# Condicionamento.net
KiCad netlist of a schematic drawn in Altium Designer
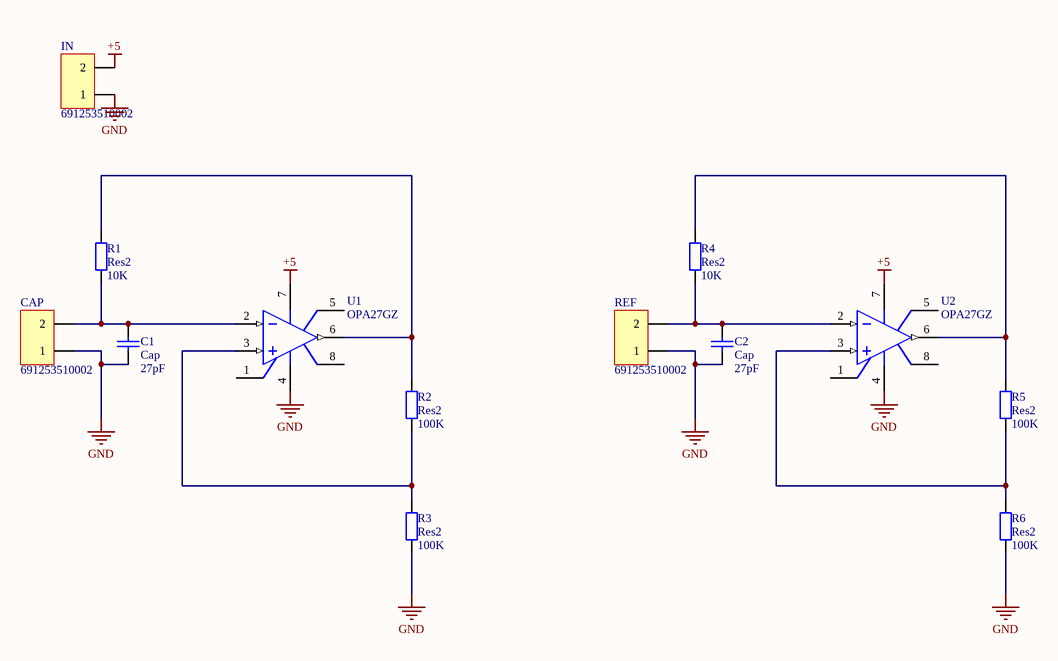
[diagram p0: Condicionamento.SchDoc]

(export (version "E")
  (design (tool "Eeschema 10.0.6"))
  (components
    (comp (ref "C1")
      (value "Cap")
      (footprint "RAD-0.3")
      (description "Capacitor")
      (fields (field (name "ALTIUM_VALUE") "27pF") (field (name "PUBLISHER") "Altium Limited"))
      (libsource (lib "Miscellaneous Devices") (part "Cap"))
    )
    (comp (ref "C2")
      (value "Cap")
      (footprint "RAD-0.3")
      (description "Capacitor")
      (fields (field (name "ALTIUM_VALUE") "27pF") (field (name "PUBLISHER") "Altium Limited"))
      (libsource (lib "Miscellaneous Devices") (part "Cap"))
    )
    (comp (ref "CAP")
      (value "691253510002")
      (footprint "691253510002")
      (description "Horizontal Cable Entry with Rising Cage Clamp, Serie 2535 - 5.08mm")
      (fields (field (name "MANUFACTURER") "Wurth Elektronik") (field (name "CREATED BY") "Baojun Chen"))
      (libsource (lib "WE_WR-TBL_Rising Cage System_5.08 mm_rev15b") (part "691253510002"))
    )
    (comp (ref "IN")
      (value "691253510002")
      (footprint "691253510002")
      (description "Horizontal Cable Entry with Rising Cage Clamp, Serie 2535 - 5.08mm")
      (fields (field (name "MANUFACTURER") "Wurth Elektronik") (field (name "CREATED BY") "Baojun Chen"))
      (libsource (lib "WE_WR-TBL_Rising Cage System_5.08 mm_rev15b") (part "691253510002"))
    )
    (comp (ref "R1")
      (value "Res2")
      (footprint "AXIAL-0.4")
      (description "Resistor")
      (fields (field (name "ALTIUM_VALUE") "10K") (field (name "PUBLISHER") "Altium Limited"))
      (libsource (lib "Miscellaneous Devices") (part "Res2"))
    )
    (comp (ref "R2")
      (value "Res2")
      (footprint "AXIAL-0.4")
      (description "Resistor")
      (fields (field (name "ALTIUM_VALUE") "100K") (field (name "PUBLISHER") "Altium Limited"))
      (libsource (lib "Miscellaneous Devices") (part "Res2"))
    )
    (comp (ref "R3")
      (value "Res2")
      (footprint "AXIAL-0.4")
      (description "Resistor")
      (fields (field (name "ALTIUM_VALUE") "100K") (field (name "PUBLISHER") "Altium Limited"))
      (libsource (lib "Miscellaneous Devices") (part "Res2"))
    )
    (comp (ref "R4")
      (value "Res2")
      (footprint "AXIAL-0.4")
      (description "Resistor")
      (fields (field (name "ALTIUM_VALUE") "10K") (field (name "PUBLISHER") "Altium Limited"))
      (libsource (lib "Miscellaneous Devices") (part "Res2"))
    )
    (comp (ref "R5")
      (value "Res2")
      (footprint "AXIAL-0.4")
      (description "Resistor")
      (fields (field (name "ALTIUM_VALUE") "100K") (field (name "PUBLISHER") "Altium Limited"))
      (libsource (lib "Miscellaneous Devices") (part "Res2"))
    )
    (comp (ref "R6")
      (value "Res2")
      (footprint "AXIAL-0.4")
      (description "Resistor")
      (fields (field (name "ALTIUM_VALUE") "100K") (field (name "PUBLISHER") "Altium Limited"))
      (libsource (lib "Miscellaneous Devices") (part "Res2"))
    )
    (comp (ref "REF")
      (value "691253510002")
      (footprint "691253510002")
      (description "Horizontal Cable Entry with Rising Cage Clamp, Serie 2535 - 5.08mm")
      (fields (field (name "MANUFACTURER") "Wurth Elektronik") (field (name "CREATED BY") "Baojun Chen"))
      (libsource (lib "WE_WR-TBL_Rising Cage System_5.08 mm_rev15b") (part "691253510002"))
    )
    (comp (ref "U1")
      (value "OPA27GZ")
      (footprint "ZZ161")
      (description "Ultra-Low-Noise Precision Operational Amplifiers")
      (fields (field (name "PUBLISHER") "Altium Limited"))
      (libsource (lib "BB Operational Amplifier") (part "OPA27GZ"))
    )
    (comp (ref "U2")
      (value "OPA27GZ")
      (footprint "ZZ161")
      (description "Ultra-Low-Noise Precision Operational Amplifiers")
      (fields (field (name "PUBLISHER") "Altium Limited"))
      (libsource (lib "BB Operational Amplifier") (part "OPA27GZ"))
    )
  )
  (nets
    (net (code "1") (name "+5") (class "Default")
      (node (ref "IN") (pin "2") (pinfunction "2_2") (pintype "passive"))
      (node (ref "U1") (pin "7") (pinfunction "V+_7") (pintype "power_in"))
      (node (ref "U2") (pin "7") (pinfunction "V+_7") (pintype "power_in"))
    )
    (net (code "2") (name "GND") (class "Default")
      (node (ref "C1") (pin "1") (pinfunction "1_1") (pintype "passive"))
      (node (ref "C2") (pin "1") (pinfunction "1_1") (pintype "passive"))
      (node (ref "CAP") (pin "1") (pinfunction "1_1") (pintype "passive"))
      (node (ref "IN") (pin "1") (pinfunction "1_1") (pintype "passive"))
      (node (ref "R3") (pin "1") (pinfunction "1_1") (pintype "passive"))
      (node (ref "R6") (pin "1") (pinfunction "1_1") (pintype "passive"))
      (node (ref "REF") (pin "1") (pinfunction "1_1") (pintype "passive"))
      (node (ref "U1") (pin "4") (pinfunction "V-_4") (pintype "power_in"))
      (node (ref "U2") (pin "4") (pinfunction "V-_4") (pintype "power_in"))
    )
    (net (code "3") (name "Net-(U1-IN+)") (class "Default")
      (node (ref "R2") (pin "1") (pinfunction "1_1") (pintype "passive"))
      (node (ref "R3") (pin "2") (pinfunction "2_2") (pintype "passive"))
      (node (ref "U1") (pin "3") (pinfunction "IN+_3") (pintype "input"))
    )
    (net (code "4") (name "Net-(U1-IN-)") (class "Default")
      (node (ref "C1") (pin "2") (pinfunction "2_2") (pintype "passive"))
      (node (ref "CAP") (pin "2") (pinfunction "2_2") (pintype "passive"))
      (node (ref "R1") (pin "1") (pinfunction "1_1") (pintype "passive"))
      (node (ref "U1") (pin "2") (pinfunction "IN-_2") (pintype "input"))
    )
    (net (code "5") (name "Net-(U1-OUT)") (class "Default")
      (node (ref "R1") (pin "2") (pinfunction "2_2") (pintype "passive"))
      (node (ref "R2") (pin "2") (pinfunction "2_2") (pintype "passive"))
      (node (ref "U1") (pin "6") (pinfunction "OUT_6") (pintype "output"))
    )
    (net (code "6") (name "Net-(U2-IN+)") (class "Default")
      (node (ref "R5") (pin "1") (pinfunction "1_1") (pintype "passive"))
      (node (ref "R6") (pin "2") (pinfunction "2_2") (pintype "passive"))
      (node (ref "U2") (pin "3") (pinfunction "IN+_3") (pintype "input"))
    )
    (net (code "7") (name "Net-(U2-IN-)") (class "Default")
      (node (ref "C2") (pin "2") (pinfunction "2_2") (pintype "passive"))
      (node (ref "R4") (pin "1") (pinfunction "1_1") (pintype "passive"))
      (node (ref "REF") (pin "2") (pinfunction "2_2") (pintype "passive"))
      (node (ref "U2") (pin "2") (pinfunction "IN-_2") (pintype "input"))
    )
    (net (code "8") (name "Net-(U2-OUT)") (class "Default")
      (node (ref "R4") (pin "2") (pinfunction "2_2") (pintype "passive"))
      (node (ref "R5") (pin "2") (pinfunction "2_2") (pintype "passive"))
      (node (ref "U2") (pin "6") (pinfunction "OUT_6") (pintype "output"))
    )
    (net (code "9") (name "unconnected-(U1-NC-Pad5)") (class "Default")
      (node (ref "U1") (pin "5") (pinfunction "NC_5") (pintype "passive"))
    )
    (net (code "10") (name "unconnected-(U1-OS_TRIM-Pad1)") (class "Default")
      (node (ref "U1") (pin "1") (pinfunction "OS_TRIM_1") (pintype "passive"))
    )
    (net (code "11") (name "unconnected-(U1-OS_TRIM-Pad8)") (class "Default")
      (node (ref "U1") (pin "8") (pinfunction "OS_TRIM_8") (pintype "passive"))
    )
    (net (code "12") (name "unconnected-(U2-NC-Pad5)") (class "Default")
      (node (ref "U2") (pin "5") (pinfunction "NC_5") (pintype "passive"))
    )
    (net (code "13") (name "unconnected-(U2-OS_TRIM-Pad1)") (class "Default")
      (node (ref "U2") (pin "1") (pinfunction "OS_TRIM_1") (pintype "passive"))
    )
    (net (code "14") (name "unconnected-(U2-OS_TRIM-Pad8)") (class "Default")
      (node (ref "U2") (pin "8") (pinfunction "OS_TRIM_8") (pintype "passive"))
    )
  )
)
